# Seri_Board_Led_v1_1.net
KiCad netlist of a schematic drawn in EAGLE
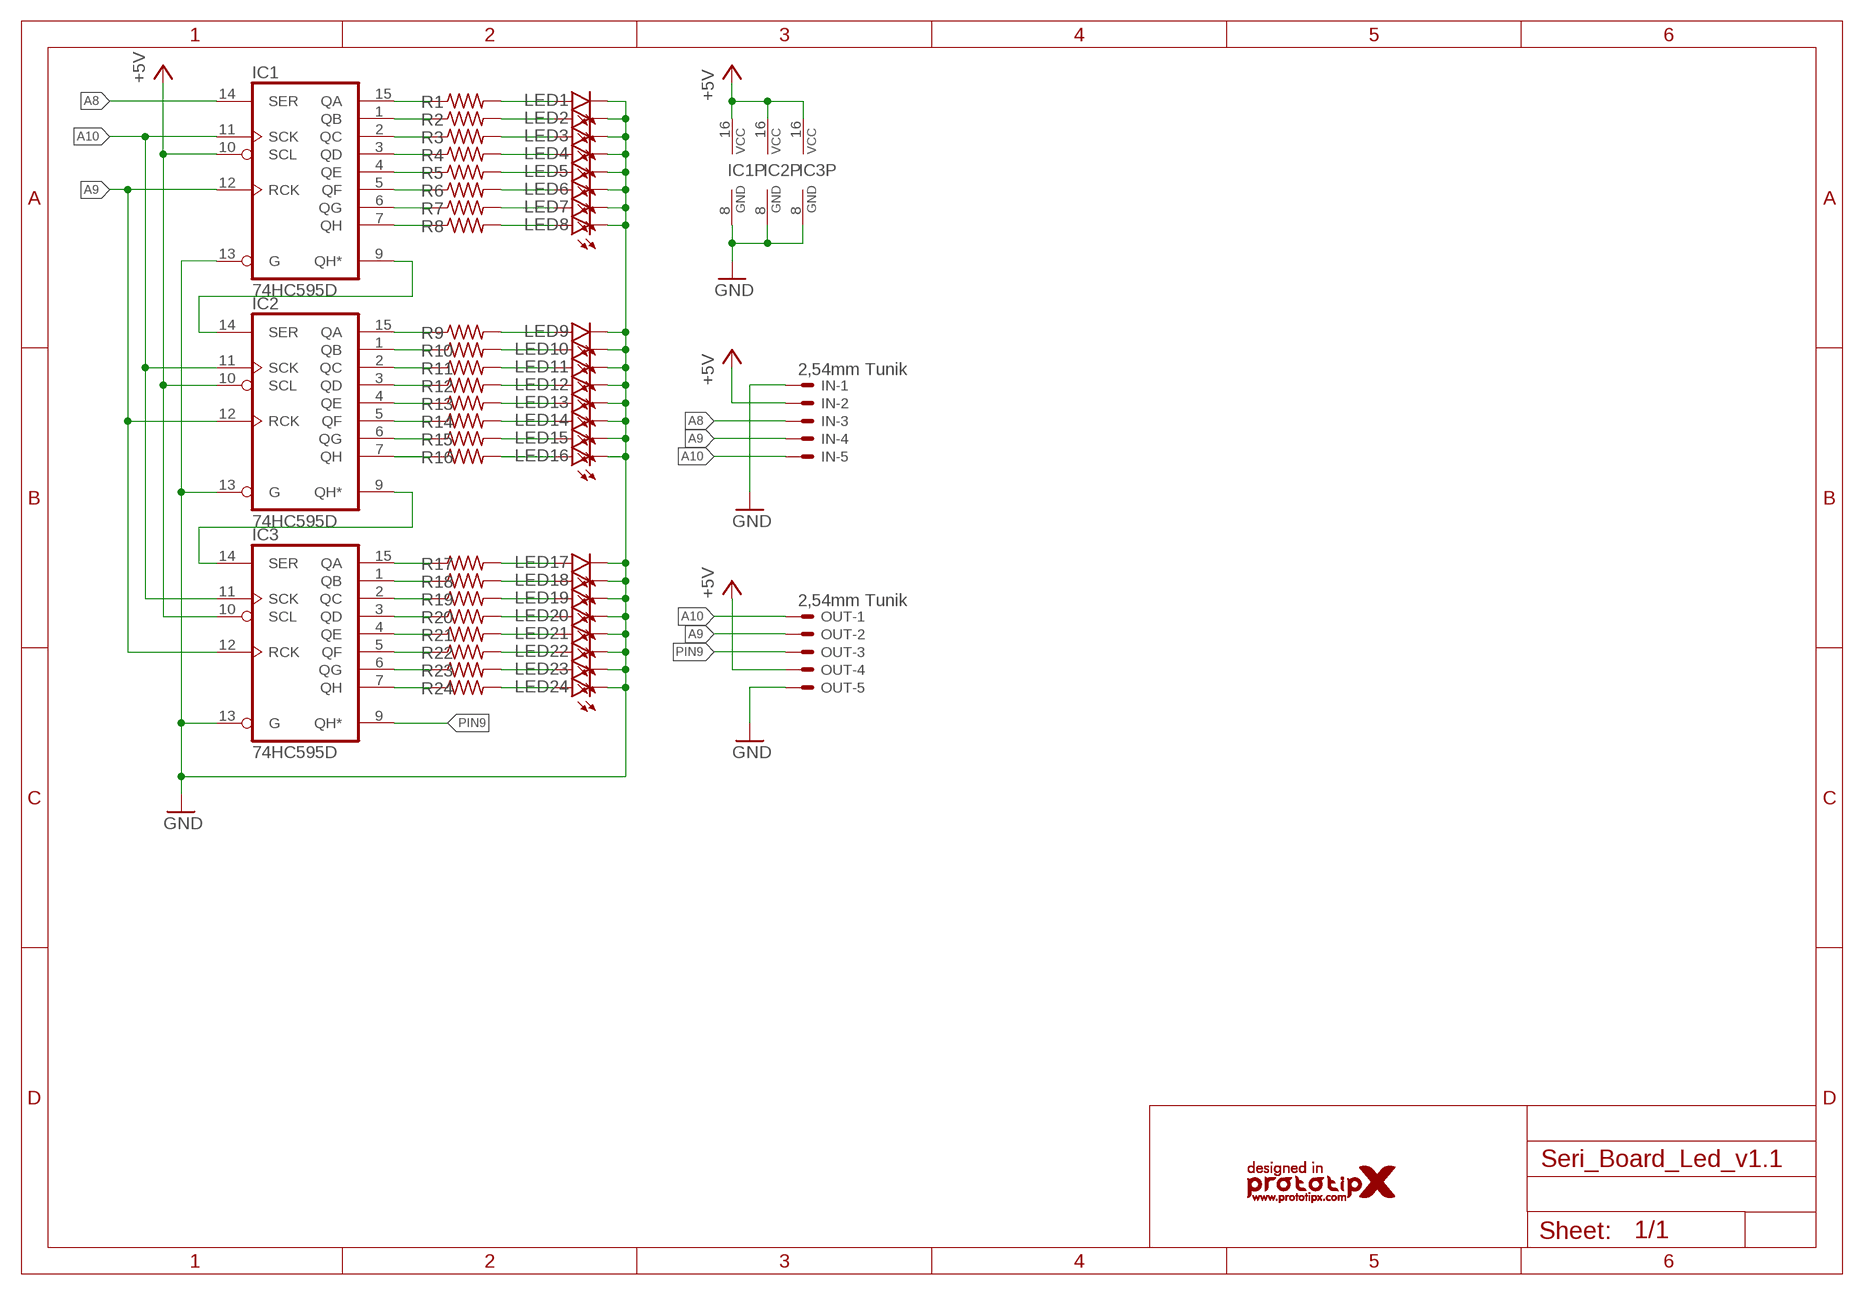
[diagram p0: schematic, sheet 1]

(export (version "E")
  (design (tool "Eeschema 10.0.6"))
  (components
    (comp (ref "IC1")
      (value "74HC595D")
      (footprint "eagle-import:SO16")
      (libsource (lib "eagle-import") (part "74595DHC"))
    )
    (comp (ref "IC2")
      (value "74HC595D")
      (footprint "eagle-import:SO16")
      (libsource (lib "eagle-import") (part "74595DHC"))
    )
    (comp (ref "IC3")
      (value "74HC595D")
      (footprint "eagle-import:SO16")
      (libsource (lib "eagle-import") (part "74595DHC"))
    )
    (comp (ref "IN")
      (value "2,54mm Tunik")
      (footprint "eagle-import:70543-05")
      (fields (field (name "MF") "MOLEX"))
      (libsource (lib "eagle-import") (part "C-GRID-05-70543"))
    )
    (comp (ref "LED1")
      (value "RED")
      (footprint "eagle-import:LED3MM")
      (libsource (lib "eagle-import") (part "LED3MM"))
    )
    (comp (ref "LED2")
      (value "RED")
      (footprint "eagle-import:LED3MM")
      (libsource (lib "eagle-import") (part "LED3MM"))
    )
    (comp (ref "LED3")
      (value "RED")
      (footprint "eagle-import:LED3MM")
      (libsource (lib "eagle-import") (part "LED3MM"))
    )
    (comp (ref "LED4")
      (value "RED")
      (footprint "eagle-import:LED3MM")
      (libsource (lib "eagle-import") (part "LED3MM"))
    )
    (comp (ref "LED5")
      (value "RED")
      (footprint "eagle-import:LED3MM")
      (libsource (lib "eagle-import") (part "LED3MM"))
    )
    (comp (ref "LED6")
      (value "RED")
      (footprint "eagle-import:LED3MM")
      (libsource (lib "eagle-import") (part "LED3MM"))
    )
    (comp (ref "LED7")
      (value "RED")
      (footprint "eagle-import:LED3MM")
      (libsource (lib "eagle-import") (part "LED3MM"))
    )
    (comp (ref "LED8")
      (value "RED")
      (footprint "eagle-import:LED3MM")
      (libsource (lib "eagle-import") (part "LED3MM"))
    )
    (comp (ref "LED9")
      (value "RED")
      (footprint "eagle-import:LED3MM")
      (libsource (lib "eagle-import") (part "LED3MM"))
    )
    (comp (ref "LED10")
      (value "RED")
      (footprint "eagle-import:LED3MM")
      (libsource (lib "eagle-import") (part "LED3MM"))
    )
    (comp (ref "LED11")
      (value "RED")
      (footprint "eagle-import:LED3MM")
      (libsource (lib "eagle-import") (part "LED3MM"))
    )
    (comp (ref "LED12")
      (value "RED")
      (footprint "eagle-import:LED3MM")
      (libsource (lib "eagle-import") (part "LED3MM"))
    )
    (comp (ref "LED13")
      (value "RED")
      (footprint "eagle-import:LED3MM")
      (libsource (lib "eagle-import") (part "LED3MM"))
    )
    (comp (ref "LED14")
      (value "RED")
      (footprint "eagle-import:LED3MM")
      (libsource (lib "eagle-import") (part "LED3MM"))
    )
    (comp (ref "LED15")
      (value "RED")
      (footprint "eagle-import:LED3MM")
      (libsource (lib "eagle-import") (part "LED3MM"))
    )
    (comp (ref "LED16")
      (value "RED")
      (footprint "eagle-import:LED3MM")
      (libsource (lib "eagle-import") (part "LED3MM"))
    )
    (comp (ref "LED17")
      (value "RED")
      (footprint "eagle-import:LED3MM")
      (libsource (lib "eagle-import") (part "LED3MM"))
    )
    (comp (ref "LED18")
      (value "RED")
      (footprint "eagle-import:LED3MM")
      (libsource (lib "eagle-import") (part "LED3MM"))
    )
    (comp (ref "LED19")
      (value "RED")
      (footprint "eagle-import:LED3MM")
      (libsource (lib "eagle-import") (part "LED3MM"))
    )
    (comp (ref "LED20")
      (value "RED")
      (footprint "eagle-import:LED3MM")
      (libsource (lib "eagle-import") (part "LED3MM"))
    )
    (comp (ref "LED21")
      (value "RED")
      (footprint "eagle-import:LED3MM")
      (libsource (lib "eagle-import") (part "LED3MM"))
    )
    (comp (ref "LED22")
      (value "RED")
      (footprint "eagle-import:LED3MM")
      (libsource (lib "eagle-import") (part "LED3MM"))
    )
    (comp (ref "LED23")
      (value "RED")
      (footprint "eagle-import:LED3MM")
      (libsource (lib "eagle-import") (part "LED3MM"))
    )
    (comp (ref "LED24")
      (value "RED")
      (footprint "eagle-import:LED3MM")
      (libsource (lib "eagle-import") (part "LED3MM"))
    )
    (comp (ref "LOGO1")
      (value "PROTOTIPXDESIGN2")
      (footprint "eagle-import:PROTOTIPX_DESING_15MM")
      (libsource (lib "eagle-import") (part "PROTOTIPXDESIGN2"))
    )
    (comp (ref "OUT")
      (value "2,54mm Tunik")
      (footprint "eagle-import:70543-05")
      (fields (field (name "MF") "MOLEX"))
      (libsource (lib "eagle-import") (part "C-GRID-05-70543"))
    )
    (comp (ref "R1")
      (value "220R")
      (footprint "eagle-import:R0805")
      (libsource (lib "eagle-import") (part "R-US_R0805"))
    )
    (comp (ref "R2")
      (value "220R")
      (footprint "eagle-import:R0805")
      (libsource (lib "eagle-import") (part "R-US_R0805"))
    )
    (comp (ref "R3")
      (value "220R")
      (footprint "eagle-import:R0805")
      (libsource (lib "eagle-import") (part "R-US_R0805"))
    )
    (comp (ref "R4")
      (value "220R")
      (footprint "eagle-import:R0805")
      (libsource (lib "eagle-import") (part "R-US_R0805"))
    )
    (comp (ref "R5")
      (value "220R")
      (footprint "eagle-import:R0805")
      (libsource (lib "eagle-import") (part "R-US_R0805"))
    )
    (comp (ref "R6")
      (value "220R")
      (footprint "eagle-import:R0805")
      (libsource (lib "eagle-import") (part "R-US_R0805"))
    )
    (comp (ref "R7")
      (value "220R")
      (footprint "eagle-import:R0805")
      (libsource (lib "eagle-import") (part "R-US_R0805"))
    )
    (comp (ref "R8")
      (value "220R")
      (footprint "eagle-import:R0805")
      (libsource (lib "eagle-import") (part "R-US_R0805"))
    )
    (comp (ref "R9")
      (value "220R")
      (footprint "eagle-import:R0805")
      (libsource (lib "eagle-import") (part "R-US_R0805"))
    )
    (comp (ref "R10")
      (value "220R")
      (footprint "eagle-import:R0805")
      (libsource (lib "eagle-import") (part "R-US_R0805"))
    )
    (comp (ref "R11")
      (value "220R")
      (footprint "eagle-import:R0805")
      (libsource (lib "eagle-import") (part "R-US_R0805"))
    )
    (comp (ref "R12")
      (value "220R")
      (footprint "eagle-import:R0805")
      (libsource (lib "eagle-import") (part "R-US_R0805"))
    )
    (comp (ref "R13")
      (value "220R")
      (footprint "eagle-import:R0805")
      (libsource (lib "eagle-import") (part "R-US_R0805"))
    )
    (comp (ref "R14")
      (value "220R")
      (footprint "eagle-import:R0805")
      (libsource (lib "eagle-import") (part "R-US_R0805"))
    )
    (comp (ref "R15")
      (value "220R")
      (footprint "eagle-import:R0805")
      (libsource (lib "eagle-import") (part "R-US_R0805"))
    )
    (comp (ref "R16")
      (value "220R")
      (footprint "eagle-import:R0805")
      (libsource (lib "eagle-import") (part "R-US_R0805"))
    )
    (comp (ref "R17")
      (value "220R")
      (footprint "eagle-import:R0805")
      (libsource (lib "eagle-import") (part "R-US_R0805"))
    )
    (comp (ref "R18")
      (value "220R")
      (footprint "eagle-import:R0805")
      (libsource (lib "eagle-import") (part "R-US_R0805"))
    )
    (comp (ref "R19")
      (value "220R")
      (footprint "eagle-import:R0805")
      (libsource (lib "eagle-import") (part "R-US_R0805"))
    )
    (comp (ref "R20")
      (value "220R")
      (footprint "eagle-import:R0805")
      (libsource (lib "eagle-import") (part "R-US_R0805"))
    )
    (comp (ref "R21")
      (value "220R")
      (footprint "eagle-import:R0805")
      (libsource (lib "eagle-import") (part "R-US_R0805"))
    )
    (comp (ref "R22")
      (value "220R")
      (footprint "eagle-import:R0805")
      (libsource (lib "eagle-import") (part "R-US_R0805"))
    )
    (comp (ref "R23")
      (value "220R")
      (footprint "eagle-import:R0805")
      (libsource (lib "eagle-import") (part "R-US_R0805"))
    )
    (comp (ref "R24")
      (value "220R")
      (footprint "eagle-import:R0805")
      (libsource (lib "eagle-import") (part "R-US_R0805"))
    )
  )
  (nets
    (net (code "1") (name "+5V") (class "Default")
      (node (ref "IC1") (pin "10") (pinfunction "SCL_10") (pintype "input"))
      (node (ref "IC1") (pin "16") (pinfunction "VCC_16") (pintype "power_in"))
      (node (ref "IC2") (pin "10") (pinfunction "SCL_10") (pintype "input"))
      (node (ref "IC2") (pin "16") (pinfunction "VCC_16") (pintype "power_in"))
      (node (ref "IC3") (pin "10") (pinfunction "SCL_10") (pintype "input"))
      (node (ref "IC3") (pin "16") (pinfunction "VCC_16") (pintype "power_in"))
      (node (ref "IN") (pin "2") (pinfunction "S_2") (pintype "passive"))
      (node (ref "OUT") (pin "4") (pinfunction "S_4") (pintype "passive"))
    )
    (net (code "2") (name "A8") (class "Default")
      (node (ref "IC1") (pin "14") (pinfunction "SER_14") (pintype "input"))
      (node (ref "IN") (pin "3") (pinfunction "S_3") (pintype "passive"))
    )
    (net (code "3") (name "A9") (class "Default")
      (node (ref "IC1") (pin "12") (pinfunction "RCK_12") (pintype "input"))
      (node (ref "IC2") (pin "12") (pinfunction "RCK_12") (pintype "input"))
      (node (ref "IC3") (pin "12") (pinfunction "RCK_12") (pintype "input"))
      (node (ref "IN") (pin "4") (pinfunction "S_4") (pintype "passive"))
      (node (ref "OUT") (pin "2") (pinfunction "S_2") (pintype "passive"))
    )
    (net (code "4") (name "A10") (class "Default")
      (node (ref "IC1") (pin "11") (pinfunction "SCK_11") (pintype "input"))
      (node (ref "IC2") (pin "11") (pinfunction "SCK_11") (pintype "input"))
      (node (ref "IC3") (pin "11") (pinfunction "SCK_11") (pintype "input"))
      (node (ref "IN") (pin "5") (pinfunction "S_5") (pintype "passive"))
      (node (ref "OUT") (pin "1") (pinfunction "S_1") (pintype "passive"))
    )
    (net (code "5") (name "GND") (class "Default")
      (node (ref "IC1") (pin "13") (pinfunction "G_13") (pintype "input"))
      (node (ref "IC1") (pin "8") (pinfunction "GND_8") (pintype "power_in"))
      (node (ref "IC2") (pin "13") (pinfunction "G_13") (pintype "input"))
      (node (ref "IC2") (pin "8") (pinfunction "GND_8") (pintype "power_in"))
      (node (ref "IC3") (pin "13") (pinfunction "G_13") (pintype "input"))
      (node (ref "IC3") (pin "8") (pinfunction "GND_8") (pintype "power_in"))
      (node (ref "IN") (pin "1") (pinfunction "S_1") (pintype "passive"))
      (node (ref "LED1") (pin "K") (pinfunction "C_K") (pintype "passive"))
      (node (ref "LED10") (pin "K") (pinfunction "C_K") (pintype "passive"))
      (node (ref "LED11") (pin "K") (pinfunction "C_K") (pintype "passive"))
      (node (ref "LED12") (pin "K") (pinfunction "C_K") (pintype "passive"))
      (node (ref "LED13") (pin "K") (pinfunction "C_K") (pintype "passive"))
      (node (ref "LED14") (pin "K") (pinfunction "C_K") (pintype "passive"))
      (node (ref "LED15") (pin "K") (pinfunction "C_K") (pintype "passive"))
      (node (ref "LED16") (pin "K") (pinfunction "C_K") (pintype "passive"))
      (node (ref "LED17") (pin "K") (pinfunction "C_K") (pintype "passive"))
      (node (ref "LED18") (pin "K") (pinfunction "C_K") (pintype "passive"))
      (node (ref "LED19") (pin "K") (pinfunction "C_K") (pintype "passive"))
      (node (ref "LED2") (pin "K") (pinfunction "C_K") (pintype "passive"))
      (node (ref "LED20") (pin "K") (pinfunction "C_K") (pintype "passive"))
      (node (ref "LED21") (pin "K") (pinfunction "C_K") (pintype "passive"))
      (node (ref "LED22") (pin "K") (pinfunction "C_K") (pintype "passive"))
      (node (ref "LED23") (pin "K") (pinfunction "C_K") (pintype "passive"))
      (node (ref "LED24") (pin "K") (pinfunction "C_K") (pintype "passive"))
      (node (ref "LED3") (pin "K") (pinfunction "C_K") (pintype "passive"))
      (node (ref "LED4") (pin "K") (pinfunction "C_K") (pintype "passive"))
      (node (ref "LED5") (pin "K") (pinfunction "C_K") (pintype "passive"))
      (node (ref "LED6") (pin "K") (pinfunction "C_K") (pintype "passive"))
      (node (ref "LED7") (pin "K") (pinfunction "C_K") (pintype "passive"))
      (node (ref "LED8") (pin "K") (pinfunction "C_K") (pintype "passive"))
      (node (ref "LED9") (pin "K") (pinfunction "C_K") (pintype "passive"))
      (node (ref "OUT") (pin "5") (pinfunction "S_5") (pintype "passive"))
    )
    (net (code "6") (name "Net-(IC1A-QA)") (class "Default")
      (node (ref "IC1") (pin "15") (pinfunction "QA_15") (pintype "tri_state"))
      (node (ref "R1") (pin "1") (pinfunction "1_1") (pintype "passive"))
    )
    (net (code "7") (name "Net-(IC1A-QB)") (class "Default")
      (node (ref "IC1") (pin "1") (pinfunction "QB_1") (pintype "tri_state"))
      (node (ref "R2") (pin "1") (pinfunction "1_1") (pintype "passive"))
    )
    (net (code "8") (name "Net-(IC1A-QC)") (class "Default")
      (node (ref "IC1") (pin "2") (pinfunction "QC_2") (pintype "tri_state"))
      (node (ref "R3") (pin "1") (pinfunction "1_1") (pintype "passive"))
    )
    (net (code "9") (name "Net-(IC1A-QD)") (class "Default")
      (node (ref "IC1") (pin "3") (pinfunction "QD_3") (pintype "tri_state"))
      (node (ref "R4") (pin "1") (pinfunction "1_1") (pintype "passive"))
    )
    (net (code "10") (name "Net-(IC1A-QE)") (class "Default")
      (node (ref "IC1") (pin "4") (pinfunction "QE_4") (pintype "tri_state"))
      (node (ref "R5") (pin "1") (pinfunction "1_1") (pintype "passive"))
    )
    (net (code "11") (name "Net-(IC1A-QF)") (class "Default")
      (node (ref "IC1") (pin "5") (pinfunction "QF_5") (pintype "tri_state"))
      (node (ref "R6") (pin "1") (pinfunction "1_1") (pintype "passive"))
    )
    (net (code "12") (name "Net-(IC1A-QG)") (class "Default")
      (node (ref "IC1") (pin "6") (pinfunction "QG_6") (pintype "tri_state"))
      (node (ref "R7") (pin "1") (pinfunction "1_1") (pintype "passive"))
    )
    (net (code "13") (name "Net-(IC1A-QH)") (class "Default")
      (node (ref "IC1") (pin "7") (pinfunction "QH_7") (pintype "tri_state"))
      (node (ref "R8") (pin "1") (pinfunction "1_1") (pintype "passive"))
    )
    (net (code "14") (name "Net-(IC1A-QH*)") (class "Default")
      (node (ref "IC1") (pin "9") (pinfunction "QH*_9") (pintype "tri_state"))
      (node (ref "IC2") (pin "14") (pinfunction "SER_14") (pintype "input"))
    )
    (net (code "15") (name "Net-(IC2A-QA)") (class "Default")
      (node (ref "IC2") (pin "15") (pinfunction "QA_15") (pintype "tri_state"))
      (node (ref "R9") (pin "1") (pinfunction "1_1") (pintype "passive"))
    )
    (net (code "16") (name "Net-(IC2A-QB)") (class "Default")
      (node (ref "IC2") (pin "1") (pinfunction "QB_1") (pintype "tri_state"))
      (node (ref "R10") (pin "1") (pinfunction "1_1") (pintype "passive"))
    )
    (net (code "17") (name "Net-(IC2A-QC)") (class "Default")
      (node (ref "IC2") (pin "2") (pinfunction "QC_2") (pintype "tri_state"))
      (node (ref "R11") (pin "1") (pinfunction "1_1") (pintype "passive"))
    )
    (net (code "18") (name "Net-(IC2A-QD)") (class "Default")
      (node (ref "IC2") (pin "3") (pinfunction "QD_3") (pintype "tri_state"))
      (node (ref "R12") (pin "1") (pinfunction "1_1") (pintype "passive"))
    )
    (net (code "19") (name "Net-(IC2A-QE)") (class "Default")
      (node (ref "IC2") (pin "4") (pinfunction "QE_4") (pintype "tri_state"))
      (node (ref "R13") (pin "1") (pinfunction "1_1") (pintype "passive"))
    )
    (net (code "20") (name "Net-(IC2A-QF)") (class "Default")
      (node (ref "IC2") (pin "5") (pinfunction "QF_5") (pintype "tri_state"))
      (node (ref "R14") (pin "1") (pinfunction "1_1") (pintype "passive"))
    )
    (net (code "21") (name "Net-(IC2A-QG)") (class "Default")
      (node (ref "IC2") (pin "6") (pinfunction "QG_6") (pintype "tri_state"))
      (node (ref "R15") (pin "1") (pinfunction "1_1") (pintype "passive"))
    )
    (net (code "22") (name "Net-(IC2A-QH)") (class "Default")
      (node (ref "IC2") (pin "7") (pinfunction "QH_7") (pintype "tri_state"))
      (node (ref "R16") (pin "1") (pinfunction "1_1") (pintype "passive"))
    )
    (net (code "23") (name "Net-(IC2A-QH*)") (class "Default")
      (node (ref "IC2") (pin "9") (pinfunction "QH*_9") (pintype "tri_state"))
      (node (ref "IC3") (pin "14") (pinfunction "SER_14") (pintype "input"))
    )
    (net (code "24") (name "Net-(IC3A-QA)") (class "Default")
      (node (ref "IC3") (pin "15") (pinfunction "QA_15") (pintype "tri_state"))
      (node (ref "R17") (pin "1") (pinfunction "1_1") (pintype "passive"))
    )
    (net (code "25") (name "Net-(IC3A-QB)") (class "Default")
      (node (ref "IC3") (pin "1") (pinfunction "QB_1") (pintype "tri_state"))
      (node (ref "R18") (pin "1") (pinfunction "1_1") (pintype "passive"))
    )
    (net (code "26") (name "Net-(IC3A-QC)") (class "Default")
      (node (ref "IC3") (pin "2") (pinfunction "QC_2") (pintype "tri_state"))
      (node (ref "R19") (pin "1") (pinfunction "1_1") (pintype "passive"))
    )
    (net (code "27") (name "Net-(IC3A-QD)") (class "Default")
      (node (ref "IC3") (pin "3") (pinfunction "QD_3") (pintype "tri_state"))
      (node (ref "R20") (pin "1") (pinfunction "1_1") (pintype "passive"))
    )
    (net (code "28") (name "Net-(IC3A-QE)") (class "Default")
      (node (ref "IC3") (pin "4") (pinfunction "QE_4") (pintype "tri_state"))
      (node (ref "R21") (pin "1") (pinfunction "1_1") (pintype "passive"))
    )
    (net (code "29") (name "Net-(IC3A-QF)") (class "Default")
      (node (ref "IC3") (pin "5") (pinfunction "QF_5") (pintype "tri_state"))
      (node (ref "R22") (pin "1") (pinfunction "1_1") (pintype "passive"))
    )
    (net (code "30") (name "Net-(IC3A-QG)") (class "Default")
      (node (ref "IC3") (pin "6") (pinfunction "QG_6") (pintype "tri_state"))
      (node (ref "R23") (pin "1") (pinfunction "1_1") (pintype "passive"))
    )
    (net (code "31") (name "Net-(IC3A-QH)") (class "Default")
      (node (ref "IC3") (pin "7") (pinfunction "QH_7") (pintype "tri_state"))
      (node (ref "R24") (pin "1") (pinfunction "1_1") (pintype "passive"))
    )
    (net (code "32") (name "Net-(LED1-PadA)") (class "Default")
      (node (ref "LED1") (pin "A") (pinfunction "A_A") (pintype "passive"))
      (node (ref "R1") (pin "2") (pinfunction "2_2") (pintype "passive"))
    )
    (net (code "33") (name "Net-(LED2-PadA)") (class "Default")
      (node (ref "LED2") (pin "A") (pinfunction "A_A") (pintype "passive"))
      (node (ref "R2") (pin "2") (pinfunction "2_2") (pintype "passive"))
    )
    (net (code "34") (name "Net-(LED3-PadA)") (class "Default")
      (node (ref "LED3") (pin "A") (pinfunction "A_A") (pintype "passive"))
      (node (ref "R3") (pin "2") (pinfunction "2_2") (pintype "passive"))
    )
    (net (code "35") (name "Net-(LED4-PadA)") (class "Default")
      (node (ref "LED4") (pin "A") (pinfunction "A_A") (pintype "passive"))
      (node (ref "R4") (pin "2") (pinfunction "2_2") (pintype "passive"))
    )
    (net (code "36") (name "Net-(LED5-PadA)") (class "Default")
      (node (ref "LED5") (pin "A") (pinfunction "A_A") (pintype "passive"))
      (node (ref "R5") (pin "2") (pinfunction "2_2") (pintype "passive"))
    )
    (net (code "37") (name "Net-(LED6-PadA)") (class "Default")
      (node (ref "LED6") (pin "A") (pinfunction "A_A") (pintype "passive"))
      (node (ref "R6") (pin "2") (pinfunction "2_2") (pintype "passive"))
    )
    (net (code "38") (name "Net-(LED7-PadA)") (class "Default")
      (node (ref "LED7") (pin "A") (pinfunction "A_A") (pintype "passive"))
      (node (ref "R7") (pin "2") (pinfunction "2_2") (pintype "passive"))
    )
    (net (code "39") (name "Net-(LED8-PadA)") (class "Default")
      (node (ref "LED8") (pin "A") (pinfunction "A_A") (pintype "passive"))
      (node (ref "R8") (pin "2") (pinfunction "2_2") (pintype "passive"))
    )
    (net (code "40") (name "Net-(LED9-PadA)") (class "Default")
      (node (ref "LED9") (pin "A") (pinfunction "A_A") (pintype "passive"))
      (node (ref "R9") (pin "2") (pinfunction "2_2") (pintype "passive"))
    )
    (net (code "41") (name "Net-(LED10-PadA)") (class "Default")
      (node (ref "LED10") (pin "A") (pinfunction "A_A") (pintype "passive"))
      (node (ref "R10") (pin "2") (pinfunction "2_2") (pintype "passive"))
    )
    (net (code "42") (name "Net-(LED11-PadA)") (class "Default")
      (node (ref "LED11") (pin "A") (pinfunction "A_A") (pintype "passive"))
      (node (ref "R11") (pin "2") (pinfunction "2_2") (pintype "passive"))
    )
    (net (code "43") (name "Net-(LED12-PadA)") (class "Default")
      (node (ref "LED12") (pin "A") (pinfunction "A_A") (pintype "passive"))
      (node (ref "R12") (pin "2") (pinfunction "2_2") (pintype "passive"))
    )
    (net (code "44") (name "Net-(LED13-PadA)") (class "Default")
      (node (ref "LED13") (pin "A") (pinfunction "A_A") (pintype "passive"))
      (node (ref "R13") (pin "2") (pinfunction "2_2") (pintype "passive"))
    )
    (net (code "45") (name "Net-(LED14-PadA)") (class "Default")
      (node (ref "LED14") (pin "A") (pinfunction "A_A") (pintype "passive"))
      (node (ref "R14") (pin "2") (pinfunction "2_2") (pintype "passive"))
    )
    (net (code "46") (name "Net-(LED15-PadA)") (class "Default")
      (node (ref "LED15") (pin "A") (pinfunction "A_A") (pintype "passive"))
      (node (ref "R15") (pin "2") (pinfunction "2_2") (pintype "passive"))
    )
    (net (code "47") (name "Net-(LED16-PadA)") (class "Default")
      (node (ref "LED16") (pin "A") (pinfunction "A_A") (pintype "passive"))
      (node (ref "R16") (pin "2") (pinfunction "2_2") (pintype "passive"))
    )
    (net (code "48") (name "Net-(LED17-PadA)") (class "Default")
      (node (ref "LED17") (pin "A") (pinfunction "A_A") (pintype "passive"))
      (node (ref "R17") (pin "2") (pinfunction "2_2") (pintype "passive"))
    )
    (net (code "49") (name "Net-(LED18-PadA)") (class "Default")
      (node (ref "LED18") (pin "A") (pinfunction "A_A") (pintype "passive"))
      (node (ref "R18") (pin "2") (pinfunction "2_2") (pintype "passive"))
    )
    (net (code "50") (name "Net-(LED19-PadA)") (class "Default")
      (node (ref "LED19") (pin "A") (pinfunction "A_A") (pintype "passive"))
      (node (ref "R19") (pin "2") (pinfunction "2_2") (pintype "passive"))
    )
    (net (code "51") (name "Net-(LED20-PadA)") (class "Default")
      (node (ref "LED20") (pin "A") (pinfunction "A_A") (pintype "passive"))
      (node (ref "R20") (pin "2") (pinfunction "2_2") (pintype "passive"))
    )
    (net (code "52") (name "Net-(LED21-PadA)") (class "Default")
      (node (ref "LED21") (pin "A") (pinfunction "A_A") (pintype "passive"))
      (node (ref "R21") (pin "2") (pinfunction "2_2") (pintype "passive"))
    )
    (net (code "53") (name "Net-(LED22-PadA)") (class "Default")
      (node (ref "LED22") (pin "A") (pinfunction "A_A") (pintype "passive"))
      (node (ref "R22") (pin "2") (pinfunction "2_2") (pintype "passive"))
    )
    (net (code "54") (name "Net-(LED23-PadA)") (class "Default")
      (node (ref "LED23") (pin "A") (pinfunction "A_A") (pintype "passive"))
      (node (ref "R23") (pin "2") (pinfunction "2_2") (pintype "passive"))
    )
    (net (code "55") (name "Net-(LED24-PadA)") (class "Default")
      (node (ref "LED24") (pin "A") (pinfunction "A_A") (pintype "passive"))
      (node (ref "R24") (pin "2") (pinfunction "2_2") (pintype "passive"))
    )
    (net (code "56") (name "PIN9") (class "Default")
      (node (ref "IC3") (pin "9") (pinfunction "QH*_9") (pintype "tri_state"))
      (node (ref "OUT") (pin "3") (pinfunction "S_3") (pintype "passive"))
    )
  )
)
